# SLT3-PAY-1Q2T_P1.net
KiCad netlist of a schematic drawn in Altium Designer
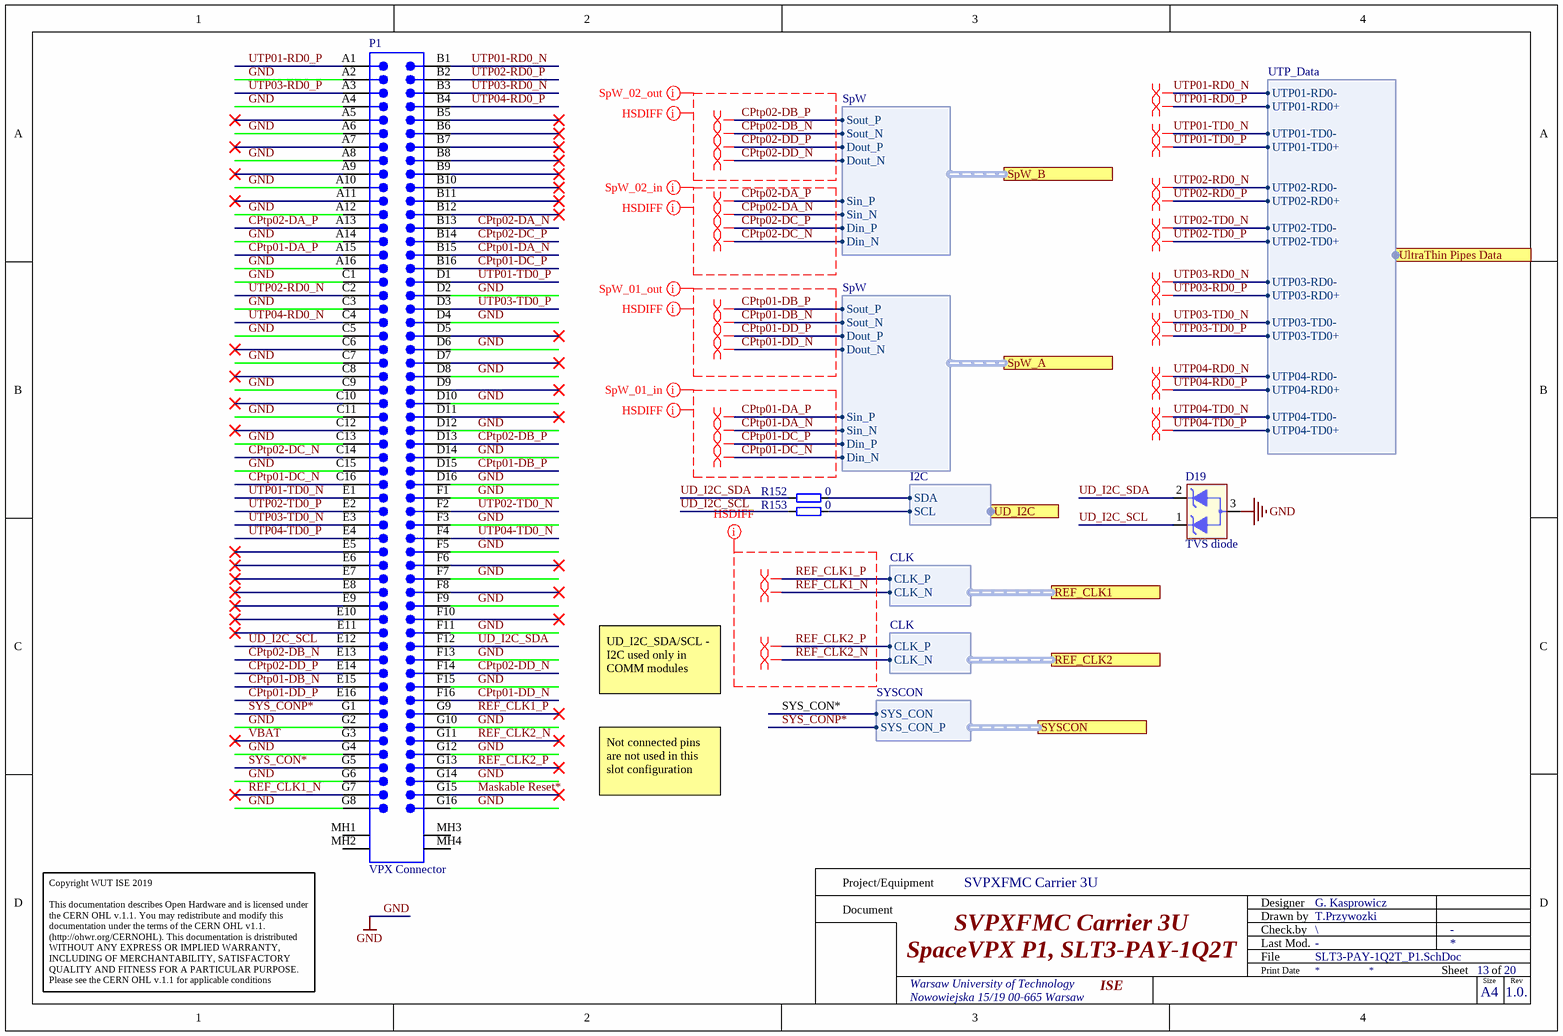
[diagram p0: SLT3-PAY-1Q2T_P1.SchDoc]

(export (version "E")
  (design (tool "Eeschema 10.0.6"))
  (components
    (comp (ref "D19")
      (value "TVS diode")
      (footprint "SOT-723_(ESD7C3.3DT5G)")
      (description "Dual TVS diode, Vrwm=3.3V")
      (fields
        (field (name "MANUFACTURER") "ON Semiconductor")
        (field (name "MANUFACTURER PART NUMBER") "ESD7C3.3DT5G")
      )
      (libsource (lib "ICs_And_Semiconductors") (part "ESD7C3.3DT5G"))
    )
    (comp (ref "P1")
      (value "VPX Connector")
      (footprint "BTB1-8-4H112M")
      (description "Ruggedized Board-to-Board Connector, Right Angle, 7-Row, Pitch 1.8mm, 112-Position")
      (fields (field (name "MANUFACTURER") "TE") (field (name "MANUFACTURER PART NUMBER") "2102771-1"))
      (libsource (lib "SVPX") (part "2102771-1"))
    )
    (comp (ref "R152")
      (value "0")
      (footprint "RESC0603X28N")
      (description "Resistor")
      (fields
        (field (name "PART NUMBER") "R0201_0R_JUMPER")
        (field (name "MANUFACTURER") "GENERIC")
        (field (name "AUTHOR") "CERN DEM JLC")
      )
      (libsource (lib "Resistors") (part "Resistor"))
    )
    (comp (ref "R153")
      (value "0")
      (footprint "RESC0603X28N")
      (description "Resistor")
      (fields
        (field (name "PART NUMBER") "R0201_0R_JUMPER")
        (field (name "MANUFACTURER") "GENERIC")
        (field (name "AUTHOR") "CERN DEM JLC")
      )
      (libsource (lib "Resistors") (part "Resistor"))
    )
  )
  (nets
    (net (code "6") (name "/CPtp01-DA_N") (class "Default")
      (node (ref "P1") (pin "B15") (pinfunction "B15_B15") (pintype "passive"))
    )
    (net (code "7") (name "/CPtp01-DA_P") (class "Default")
      (node (ref "P1") (pin "A15") (pinfunction "A15_A15") (pintype "passive"))
    )
    (net (code "8") (name "/CPtp01-DB_N") (class "Default")
      (node (ref "P1") (pin "E15") (pinfunction "E15_E15") (pintype "passive"))
    )
    (net (code "9") (name "/CPtp01-DB_P") (class "Default")
      (node (ref "P1") (pin "D15") (pinfunction "D15_D15") (pintype "passive"))
    )
    (net (code "10") (name "/CPtp01-DC_N") (class "Default")
      (node (ref "P1") (pin "C16") (pinfunction "C16_C16") (pintype "passive"))
    )
    (net (code "11") (name "/CPtp01-DC_P") (class "Default")
      (node (ref "P1") (pin "B16") (pinfunction "B16_B16") (pintype "passive"))
    )
    (net (code "12") (name "/CPtp01-DD_N") (class "Default")
      (node (ref "P1") (pin "F16") (pinfunction "F16_F16") (pintype "passive"))
    )
    (net (code "13") (name "/CPtp01-DD_P") (class "Default")
      (node (ref "P1") (pin "E16") (pinfunction "E16_E16") (pintype "passive"))
    )
    (net (code "14") (name "/CPtp02-DA_N") (class "Default")
      (node (ref "P1") (pin "B13") (pinfunction "B13_B13") (pintype "passive"))
    )
    (net (code "15") (name "/CPtp02-DA_P") (class "Default")
      (node (ref "P1") (pin "A13") (pinfunction "A13_A13") (pintype "passive"))
    )
    (net (code "16") (name "/CPtp02-DB_N") (class "Default")
      (node (ref "P1") (pin "E13") (pinfunction "E13_E13") (pintype "passive"))
    )
    (net (code "17") (name "/CPtp02-DB_P") (class "Default")
      (node (ref "P1") (pin "D13") (pinfunction "D13_D13") (pintype "passive"))
    )
    (net (code "18") (name "/CPtp02-DC_N") (class "Default")
      (node (ref "P1") (pin "C14") (pinfunction "C14_C14") (pintype "passive"))
    )
    (net (code "19") (name "/CPtp02-DC_P") (class "Default")
      (node (ref "P1") (pin "B14") (pinfunction "B14_B14") (pintype "passive"))
    )
    (net (code "20") (name "/CPtp02-DD_N") (class "Default")
      (node (ref "P1") (pin "F14") (pinfunction "F14_F14") (pintype "passive"))
    )
    (net (code "21") (name "/CPtp02-DD_P") (class "Default")
      (node (ref "P1") (pin "E14") (pinfunction "E14_E14") (pintype "passive"))
    )
    (net (code "22") (name "/Maskable Reset*") (class "Default")
      (node (ref "P1") (pin "G15") (pinfunction "G15_G15") (pintype "passive+no_connect"))
    )
    (net (code "23") (name "/REF_CLK1_N") (class "Default")
      (node (ref "P1") (pin "G7") (pinfunction "G7_G7") (pintype "passive"))
    )
    (net (code "24") (name "/REF_CLK1_P") (class "Default")
      (node (ref "P1") (pin "G9") (pinfunction "G9_G9") (pintype "passive"))
    )
    (net (code "25") (name "/REF_CLK2_N") (class "Default")
      (node (ref "P1") (pin "G11") (pinfunction "G11_G11") (pintype "passive"))
    )
    (net (code "26") (name "/REF_CLK2_P") (class "Default")
      (node (ref "P1") (pin "G13") (pinfunction "G13_G13") (pintype "passive"))
    )
    (net (code "27") (name "/SYS_CON*") (class "Default")
      (node (ref "P1") (pin "G5") (pinfunction "G5_G5") (pintype "passive"))
    )
    (net (code "28") (name "/SYS_CONP*") (class "Default")
      (node (ref "P1") (pin "G1") (pinfunction "G1_G1") (pintype "passive"))
    )
    (net (code "29") (name "/UD_I2C_SCL") (class "Default")
      (node (ref "D19") (pin "1") (pinfunction "1_1") (pintype "passive"))
      (node (ref "P1") (pin "E12") (pinfunction "E12_E12") (pintype "passive"))
      (node (ref "R153") (pin "1") (pinfunction "1_1") (pintype "passive"))
    )
    (net (code "30") (name "/UD_I2C_SDA") (class "Default")
      (node (ref "D19") (pin "2") (pinfunction "2_2") (pintype "passive"))
      (node (ref "P1") (pin "F12") (pinfunction "F12_F12") (pintype "passive"))
      (node (ref "R152") (pin "1") (pinfunction "1_1") (pintype "passive"))
    )
    (net (code "31") (name "/UTP01-RD0_N") (class "Default")
      (node (ref "P1") (pin "B1") (pinfunction "B1_B1") (pintype "passive"))
    )
    (net (code "32") (name "/UTP01-RD0_P") (class "Default")
      (node (ref "P1") (pin "A1") (pinfunction "A1_A1") (pintype "passive"))
    )
    (net (code "33") (name "/UTP01-TD0_N") (class "Default")
      (node (ref "P1") (pin "E1") (pinfunction "E1_E1") (pintype "passive"))
    )
    (net (code "34") (name "/UTP01-TD0_P") (class "Default")
      (node (ref "P1") (pin "D1") (pinfunction "D1_D1") (pintype "passive"))
    )
    (net (code "35") (name "/UTP02-RD0_N") (class "Default")
      (node (ref "P1") (pin "C2") (pinfunction "C2_C2") (pintype "passive"))
    )
    (net (code "36") (name "/UTP02-RD0_P") (class "Default")
      (node (ref "P1") (pin "B2") (pinfunction "B2_B2") (pintype "passive"))
    )
    (net (code "37") (name "/UTP02-TD0_N") (class "Default")
      (node (ref "P1") (pin "F2") (pinfunction "F2_F2") (pintype "passive"))
    )
    (net (code "38") (name "/UTP02-TD0_P") (class "Default")
      (node (ref "P1") (pin "E2") (pinfunction "E2_E2") (pintype "passive"))
    )
    (net (code "39") (name "/UTP03-RD0_N") (class "Default")
      (node (ref "P1") (pin "B3") (pinfunction "B3_B3") (pintype "passive"))
    )
    (net (code "40") (name "/UTP03-RD0_P") (class "Default")
      (node (ref "P1") (pin "A3") (pinfunction "A3_A3") (pintype "passive"))
    )
    (net (code "41") (name "/UTP03-TD0_N") (class "Default")
      (node (ref "P1") (pin "E3") (pinfunction "E3_E3") (pintype "passive"))
    )
    (net (code "42") (name "/UTP03-TD0_P") (class "Default")
      (node (ref "P1") (pin "D3") (pinfunction "D3_D3") (pintype "passive"))
    )
    (net (code "43") (name "/UTP04-RD0_N") (class "Default")
      (node (ref "P1") (pin "C4") (pinfunction "C4_C4") (pintype "passive"))
    )
    (net (code "44") (name "/UTP04-RD0_P") (class "Default")
      (node (ref "P1") (pin "B4") (pinfunction "B4_B4") (pintype "passive"))
    )
    (net (code "45") (name "/UTP04-TD0_N") (class "Default")
      (node (ref "P1") (pin "F4") (pinfunction "F4_F4") (pintype "passive"))
    )
    (net (code "46") (name "/UTP04-TD0_P") (class "Default")
      (node (ref "P1") (pin "E4") (pinfunction "E4_E4") (pintype "passive"))
    )
    (net (code "47") (name "/VBAT") (class "Default")
      (node (ref "P1") (pin "G3") (pinfunction "G3_G3") (pintype "passive+no_connect"))
    )
    (net (code "53") (name "GND") (class "Default")
      (node (ref "D19") (pin "3") (pinfunction "3_3") (pintype "passive"))
      (node (ref "P1") (pin "A10") (pinfunction "A10_A10") (pintype "passive"))
      (node (ref "P1") (pin "A12") (pinfunction "A12_A12") (pintype "passive"))
      (node (ref "P1") (pin "A14") (pinfunction "A14_A14") (pintype "passive"))
      (node (ref "P1") (pin "A16") (pinfunction "A16_A16") (pintype "passive"))
      (node (ref "P1") (pin "A2") (pinfunction "A2_A2") (pintype "passive"))
      (node (ref "P1") (pin "A4") (pinfunction "A4_A4") (pintype "passive"))
      (node (ref "P1") (pin "A6") (pinfunction "A6_A6") (pintype "passive"))
      (node (ref "P1") (pin "A8") (pinfunction "A8_A8") (pintype "passive"))
      (node (ref "P1") (pin "C1") (pinfunction "C1_C1") (pintype "passive"))
      (node (ref "P1") (pin "C11") (pinfunction "C11_C11") (pintype "passive"))
      (node (ref "P1") (pin "C13") (pinfunction "C13_C13") (pintype "passive"))
      (node (ref "P1") (pin "C15") (pinfunction "C15_C15") (pintype "passive"))
      (node (ref "P1") (pin "C3") (pinfunction "C3_C3") (pintype "passive"))
      (node (ref "P1") (pin "C5") (pinfunction "C5_C5") (pintype "passive"))
      (node (ref "P1") (pin "C7") (pinfunction "C7_C7") (pintype "passive"))
      (node (ref "P1") (pin "C9") (pinfunction "C9_C9") (pintype "passive"))
      (node (ref "P1") (pin "D10") (pinfunction "D10_D10") (pintype "passive"))
      (node (ref "P1") (pin "D12") (pinfunction "D12_D12") (pintype "passive"))
      (node (ref "P1") (pin "D14") (pinfunction "D14_D14") (pintype "passive"))
      (node (ref "P1") (pin "D16") (pinfunction "D16_D16") (pintype "passive"))
      (node (ref "P1") (pin "D2") (pinfunction "D2_D2") (pintype "passive"))
      (node (ref "P1") (pin "D4") (pinfunction "D4_D4") (pintype "passive"))
      (node (ref "P1") (pin "D6") (pinfunction "D6_D6") (pintype "passive"))
      (node (ref "P1") (pin "D8") (pinfunction "D8_D8") (pintype "passive"))
      (node (ref "P1") (pin "F1") (pinfunction "F1_F1") (pintype "passive"))
      (node (ref "P1") (pin "F11") (pinfunction "F11_F11") (pintype "passive"))
      (node (ref "P1") (pin "F13") (pinfunction "F13_F13") (pintype "passive"))
      (node (ref "P1") (pin "F15") (pinfunction "F15_F15") (pintype "passive"))
      (node (ref "P1") (pin "F3") (pinfunction "F3_F3") (pintype "passive"))
      (node (ref "P1") (pin "F5") (pinfunction "F5_F5") (pintype "passive"))
      (node (ref "P1") (pin "F7") (pinfunction "F7_F7") (pintype "passive"))
      (node (ref "P1") (pin "F9") (pinfunction "F9_F9") (pintype "passive"))
      (node (ref "P1") (pin "G10") (pinfunction "G10_G10") (pintype "passive"))
      (node (ref "P1") (pin "G12") (pinfunction "G12_G12") (pintype "passive"))
      (node (ref "P1") (pin "G14") (pinfunction "G14_G14") (pintype "passive"))
      (node (ref "P1") (pin "G16") (pinfunction "G16_G16") (pintype "passive"))
      (node (ref "P1") (pin "G2") (pinfunction "G2_G2") (pintype "passive"))
      (node (ref "P1") (pin "G4") (pinfunction "G4_G4") (pintype "passive"))
      (node (ref "P1") (pin "G6") (pinfunction "G6_G6") (pintype "passive"))
      (node (ref "P1") (pin "G8") (pinfunction "G8_G8") (pintype "passive"))
    )
    (net (code "54") (name "unconnected-(P1-PadA5)") (class "Default")
      (node (ref "P1") (pin "A5") (pinfunction "A5_A5") (pintype "passive+no_connect"))
    )
    (net (code "55") (name "unconnected-(P1-PadA7)") (class "Default")
      (node (ref "P1") (pin "A7") (pinfunction "A7_A7") (pintype "passive+no_connect"))
    )
    (net (code "56") (name "unconnected-(P1-PadA9)") (class "Default")
      (node (ref "P1") (pin "A9") (pinfunction "A9_A9") (pintype "passive+no_connect"))
    )
    (net (code "57") (name "unconnected-(P1-PadA11)") (class "Default")
      (node (ref "P1") (pin "A11") (pinfunction "A11_A11") (pintype "passive+no_connect"))
    )
    (net (code "58") (name "unconnected-(P1-PadB5)") (class "Default")
      (node (ref "P1") (pin "B5") (pinfunction "B5_B5") (pintype "passive+no_connect"))
    )
    (net (code "59") (name "unconnected-(P1-PadB6)") (class "Default")
      (node (ref "P1") (pin "B6") (pinfunction "B6_B6") (pintype "passive+no_connect"))
    )
    (net (code "60") (name "unconnected-(P1-PadB7)") (class "Default")
      (node (ref "P1") (pin "B7") (pinfunction "B7_B7") (pintype "passive+no_connect"))
    )
    (net (code "61") (name "unconnected-(P1-PadB8)") (class "Default")
      (node (ref "P1") (pin "B8") (pinfunction "B8_B8") (pintype "passive+no_connect"))
    )
    (net (code "62") (name "unconnected-(P1-PadB9)") (class "Default")
      (node (ref "P1") (pin "B9") (pinfunction "B9_B9") (pintype "passive+no_connect"))
    )
    (net (code "63") (name "unconnected-(P1-PadB10)") (class "Default")
      (node (ref "P1") (pin "B10") (pinfunction "B10_B10") (pintype "passive+no_connect"))
    )
    (net (code "64") (name "unconnected-(P1-PadB11)") (class "Default")
      (node (ref "P1") (pin "B11") (pinfunction "B11_B11") (pintype "passive+no_connect"))
    )
    (net (code "65") (name "unconnected-(P1-PadB12)") (class "Default")
      (node (ref "P1") (pin "B12") (pinfunction "B12_B12") (pintype "passive+no_connect"))
    )
    (net (code "66") (name "unconnected-(P1-PadC6)") (class "Default")
      (node (ref "P1") (pin "C6") (pinfunction "C6_C6") (pintype "passive+no_connect"))
    )
    (net (code "67") (name "unconnected-(P1-PadC8)") (class "Default")
      (node (ref "P1") (pin "C8") (pinfunction "C8_C8") (pintype "passive+no_connect"))
    )
    (net (code "68") (name "unconnected-(P1-PadC10)") (class "Default")
      (node (ref "P1") (pin "C10") (pinfunction "C10_C10") (pintype "passive+no_connect"))
    )
    (net (code "69") (name "unconnected-(P1-PadC12)") (class "Default")
      (node (ref "P1") (pin "C12") (pinfunction "C12_C12") (pintype "passive+no_connect"))
    )
    (net (code "70") (name "unconnected-(P1-PadD5)") (class "Default")
      (node (ref "P1") (pin "D5") (pinfunction "D5_D5") (pintype "passive+no_connect"))
    )
    (net (code "71") (name "unconnected-(P1-PadD7)") (class "Default")
      (node (ref "P1") (pin "D7") (pinfunction "D7_D7") (pintype "passive+no_connect"))
    )
    (net (code "72") (name "unconnected-(P1-PadD9)") (class "Default")
      (node (ref "P1") (pin "D9") (pinfunction "D9_D9") (pintype "passive+no_connect"))
    )
    (net (code "73") (name "unconnected-(P1-PadD11)") (class "Default")
      (node (ref "P1") (pin "D11") (pinfunction "D11_D11") (pintype "passive+no_connect"))
    )
    (net (code "74") (name "unconnected-(P1-PadE5)") (class "Default")
      (node (ref "P1") (pin "E5") (pinfunction "E5_E5") (pintype "passive+no_connect"))
    )
    (net (code "75") (name "unconnected-(P1-PadE6)") (class "Default")
      (node (ref "P1") (pin "E6") (pinfunction "E6_E6") (pintype "passive+no_connect"))
    )
    (net (code "76") (name "unconnected-(P1-PadE7)") (class "Default")
      (node (ref "P1") (pin "E7") (pinfunction "E7_E7") (pintype "passive+no_connect"))
    )
    (net (code "77") (name "unconnected-(P1-PadE8)") (class "Default")
      (node (ref "P1") (pin "E8") (pinfunction "E8_E8") (pintype "passive+no_connect"))
    )
    (net (code "78") (name "unconnected-(P1-PadE9)") (class "Default")
      (node (ref "P1") (pin "E9") (pinfunction "E9_E9") (pintype "passive+no_connect"))
    )
    (net (code "79") (name "unconnected-(P1-PadE10)") (class "Default")
      (node (ref "P1") (pin "E10") (pinfunction "E10_E10") (pintype "passive+no_connect"))
    )
    (net (code "80") (name "unconnected-(P1-PadE11)") (class "Default")
      (node (ref "P1") (pin "E11") (pinfunction "E11_E11") (pintype "passive+no_connect"))
    )
    (net (code "81") (name "unconnected-(P1-PadF6)") (class "Default")
      (node (ref "P1") (pin "F6") (pinfunction "F6_F6") (pintype "passive+no_connect"))
    )
    (net (code "82") (name "unconnected-(P1-PadF8)") (class "Default")
      (node (ref "P1") (pin "F8") (pinfunction "F8_F8") (pintype "passive+no_connect"))
    )
    (net (code "83") (name "unconnected-(P1-PadF10)") (class "Default")
      (node (ref "P1") (pin "F10") (pinfunction "F10_F10") (pintype "passive+no_connect"))
    )
    (net (code "84") (name "unconnected-(P1-PadMH1)") (class "Default")
      (node (ref "P1") (pin "MH1") (pinfunction "MH1_MH1") (pintype "passive"))
    )
    (net (code "85") (name "unconnected-(P1-PadMH2)") (class "Default")
      (node (ref "P1") (pin "MH2") (pinfunction "MH2_MH2") (pintype "passive"))
    )
    (net (code "86") (name "unconnected-(P1-PadMH3)") (class "Default")
      (node (ref "P1") (pin "MH3") (pinfunction "MH3_MH3") (pintype "passive"))
    )
    (net (code "87") (name "unconnected-(P1-PadMH4)") (class "Default")
      (node (ref "P1") (pin "MH4") (pinfunction "MH4_MH4") (pintype "passive"))
    )
    (net (code "88") (name "unconnected-(R152-Pad2)") (class "Default")
      (node (ref "R152") (pin "2") (pinfunction "2_2") (pintype "passive"))
    )
    (net (code "89") (name "unconnected-(R153-Pad2)") (class "Default")
      (node (ref "R153") (pin "2") (pinfunction "2_2") (pintype "passive"))
    )
  )
)
